# Rain_Module_SCH.net
KiCad netlist of a schematic drawn in Altium Designer
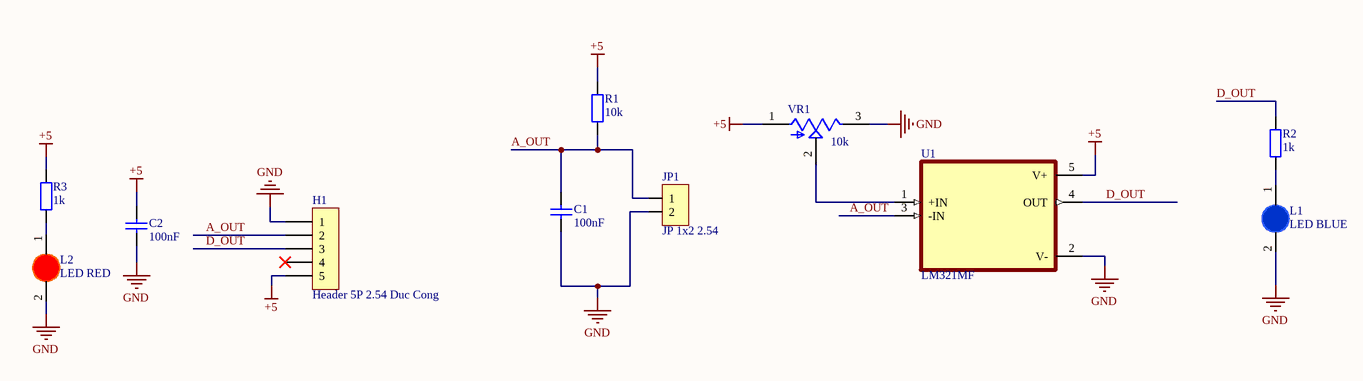
[diagram p0: Rain Module_SCH.SchDoc]

(export (version "E")
  (design (tool "Eeschema 10.0.6"))
  (components
    (comp (ref "C1")
      (value "100nF")
      (footprint "tu 0603")
      (description "Dán")
      (libsource (lib "namnt_Lib") (part "Tu 0603 104 50V 10%"))
    )
    (comp (ref "C2")
      (value "100nF")
      (footprint "tu 0603")
      (description "Dán")
      (libsource (lib "namnt_Lib") (part "Tu 0603 104 50V 10%"))
    )
    (comp (ref "H1")
      (value "Header 5P 2.54 Duc Cong")
      (footprint "Header 5P DC 2.54")
      (description "Cắm")
      (libsource (lib "namnt_Lib") (part "Header 5P 2.54 Duc Cong"))
    )
    (comp (ref "JP1")
      (value "JP 1x2 2.54")
      (footprint "JP 1x2 DC")
      (description "Cắm")
      (libsource (lib "namnt_Lib") (part "JP 1x2 2.54 Duc Cong"))
    )
    (comp (ref "L1")
      (value "LED BLUE")
      (footprint "LED-0805-Blue")
      (description "Dán")
      (libsource (lib "namnt_Lib") (part "LED 0805 Xanh Duong"))
    )
    (comp (ref "L2")
      (value "LED RED")
      (footprint "LED-0805-Red")
      (description "Dán")
      (libsource (lib "namnt_Lib") (part "LED 0805 Do"))
    )
    (comp (ref "R1")
      (value "10k")
      (footprint "tro smd 0603")
      (description "Dán")
      (libsource (lib "namnt_Lib") (part "Tro 0603 1% 10k"))
    )
    (comp (ref "R2")
      (value "1k")
      (footprint "tro smd 0603")
      (description "Dán")
      (libsource (lib "namnt_Lib") (part "Tro 0603 1% 1k"))
    )
    (comp (ref "R3")
      (value "1k")
      (footprint "tro smd 0603")
      (description "Dán")
      (libsource (lib "namnt_Lib") (part "Tro 0603 1% 1k"))
    )
    (comp (ref "U1")
      (value "LM321MF")
      (footprint "SOT95P280X145-5N")
      (description "Low Power Single Op Amp 5-SOT-23 -40 to 85")
      (fields (field (name "MF") "Texas Instruments"))
      (libsource (lib "namnt_Lib") (part "LM321MF"))
    )
    (comp (ref "VR1")
      (value "10k")
      (footprint "TRIM_3362P-1-102")
      (description "TRIMMER - 1/4in SQ ST CERMET ¦ Bourns 3362P-1-102")
      (fields (field (name "MF") "Bourns") (field (name "MP") "3362P-1-102"))
      (libsource (lib "namnt_Lib") (part "Bien tro vuong"))
    )
  )
  (nets
    (net (code "1") (name "+5") (class "Default")
      (node (ref "C2") (pin "1") (pinfunction "1_1") (pintype "passive"))
      (node (ref "H1") (pin "5") (pinfunction "5_5") (pintype "passive"))
      (node (ref "R1") (pin "2") (pinfunction "2_2") (pintype "passive"))
      (node (ref "R3") (pin "2") (pinfunction "2_2") (pintype "passive"))
      (node (ref "U1") (pin "5") (pinfunction "V+_5") (pintype "power_in"))
      (node (ref "VR1") (pin "1") (pinfunction "CCW_1") (pintype "passive"))
    )
    (net (code "2") (name "/A_OUT") (class "Default")
      (node (ref "C1") (pin "1") (pinfunction "1_1") (pintype "passive"))
      (node (ref "H1") (pin "2") (pinfunction "2_2") (pintype "passive"))
      (node (ref "JP1") (pin "1") (pinfunction "1_1") (pintype "passive"))
      (node (ref "R1") (pin "1") (pinfunction "1_1") (pintype "passive"))
      (node (ref "U1") (pin "3") (pinfunction "-IN_3") (pintype "input"))
    )
    (net (code "3") (name "/D_OUT") (class "Default")
      (node (ref "H1") (pin "3") (pinfunction "3_3") (pintype "passive"))
      (node (ref "R2") (pin "2") (pinfunction "2_2") (pintype "passive"))
      (node (ref "U1") (pin "4") (pinfunction "OUT_4") (pintype "output"))
    )
    (net (code "4") (name "GND") (class "Default")
      (node (ref "C1") (pin "2") (pinfunction "2_2") (pintype "passive"))
      (node (ref "C2") (pin "2") (pinfunction "2_2") (pintype "passive"))
      (node (ref "H1") (pin "1") (pinfunction "1_1") (pintype "passive"))
      (node (ref "JP1") (pin "2") (pinfunction "2_2") (pintype "passive"))
      (node (ref "L1") (pin "2") (pinfunction "K_2") (pintype "passive"))
      (node (ref "L2") (pin "2") (pinfunction "K_2") (pintype "passive"))
      (node (ref "U1") (pin "2") (pinfunction "V-_2") (pintype "power_in"))
      (node (ref "VR1") (pin "3") (pinfunction "CW_3") (pintype "passive"))
    )
    (net (code "5") (name "Net-(L1-A)") (class "Default")
      (node (ref "L1") (pin "1") (pinfunction "A_1") (pintype "passive"))
      (node (ref "R2") (pin "1") (pinfunction "1_1") (pintype "passive"))
    )
    (net (code "6") (name "Net-(L2-A)") (class "Default")
      (node (ref "L2") (pin "1") (pinfunction "A_1") (pintype "passive"))
      (node (ref "R3") (pin "1") (pinfunction "1_1") (pintype "passive"))
    )
    (net (code "7") (name "Net-(U1-+IN)") (class "Default")
      (node (ref "U1") (pin "1") (pinfunction "+IN_1") (pintype "input"))
      (node (ref "VR1") (pin "2") (pinfunction "WIPER_2") (pintype "passive"))
    )
    (net (code "8") (name "unconnected-(H1-Pad4)") (class "Default")
      (node (ref "H1") (pin "4") (pinfunction "4_4") (pintype "passive+no_connect"))
    )
  )
)
